# PG03__Qseven_Connector.net
KiCad netlist of a schematic drawn in Altium Designer
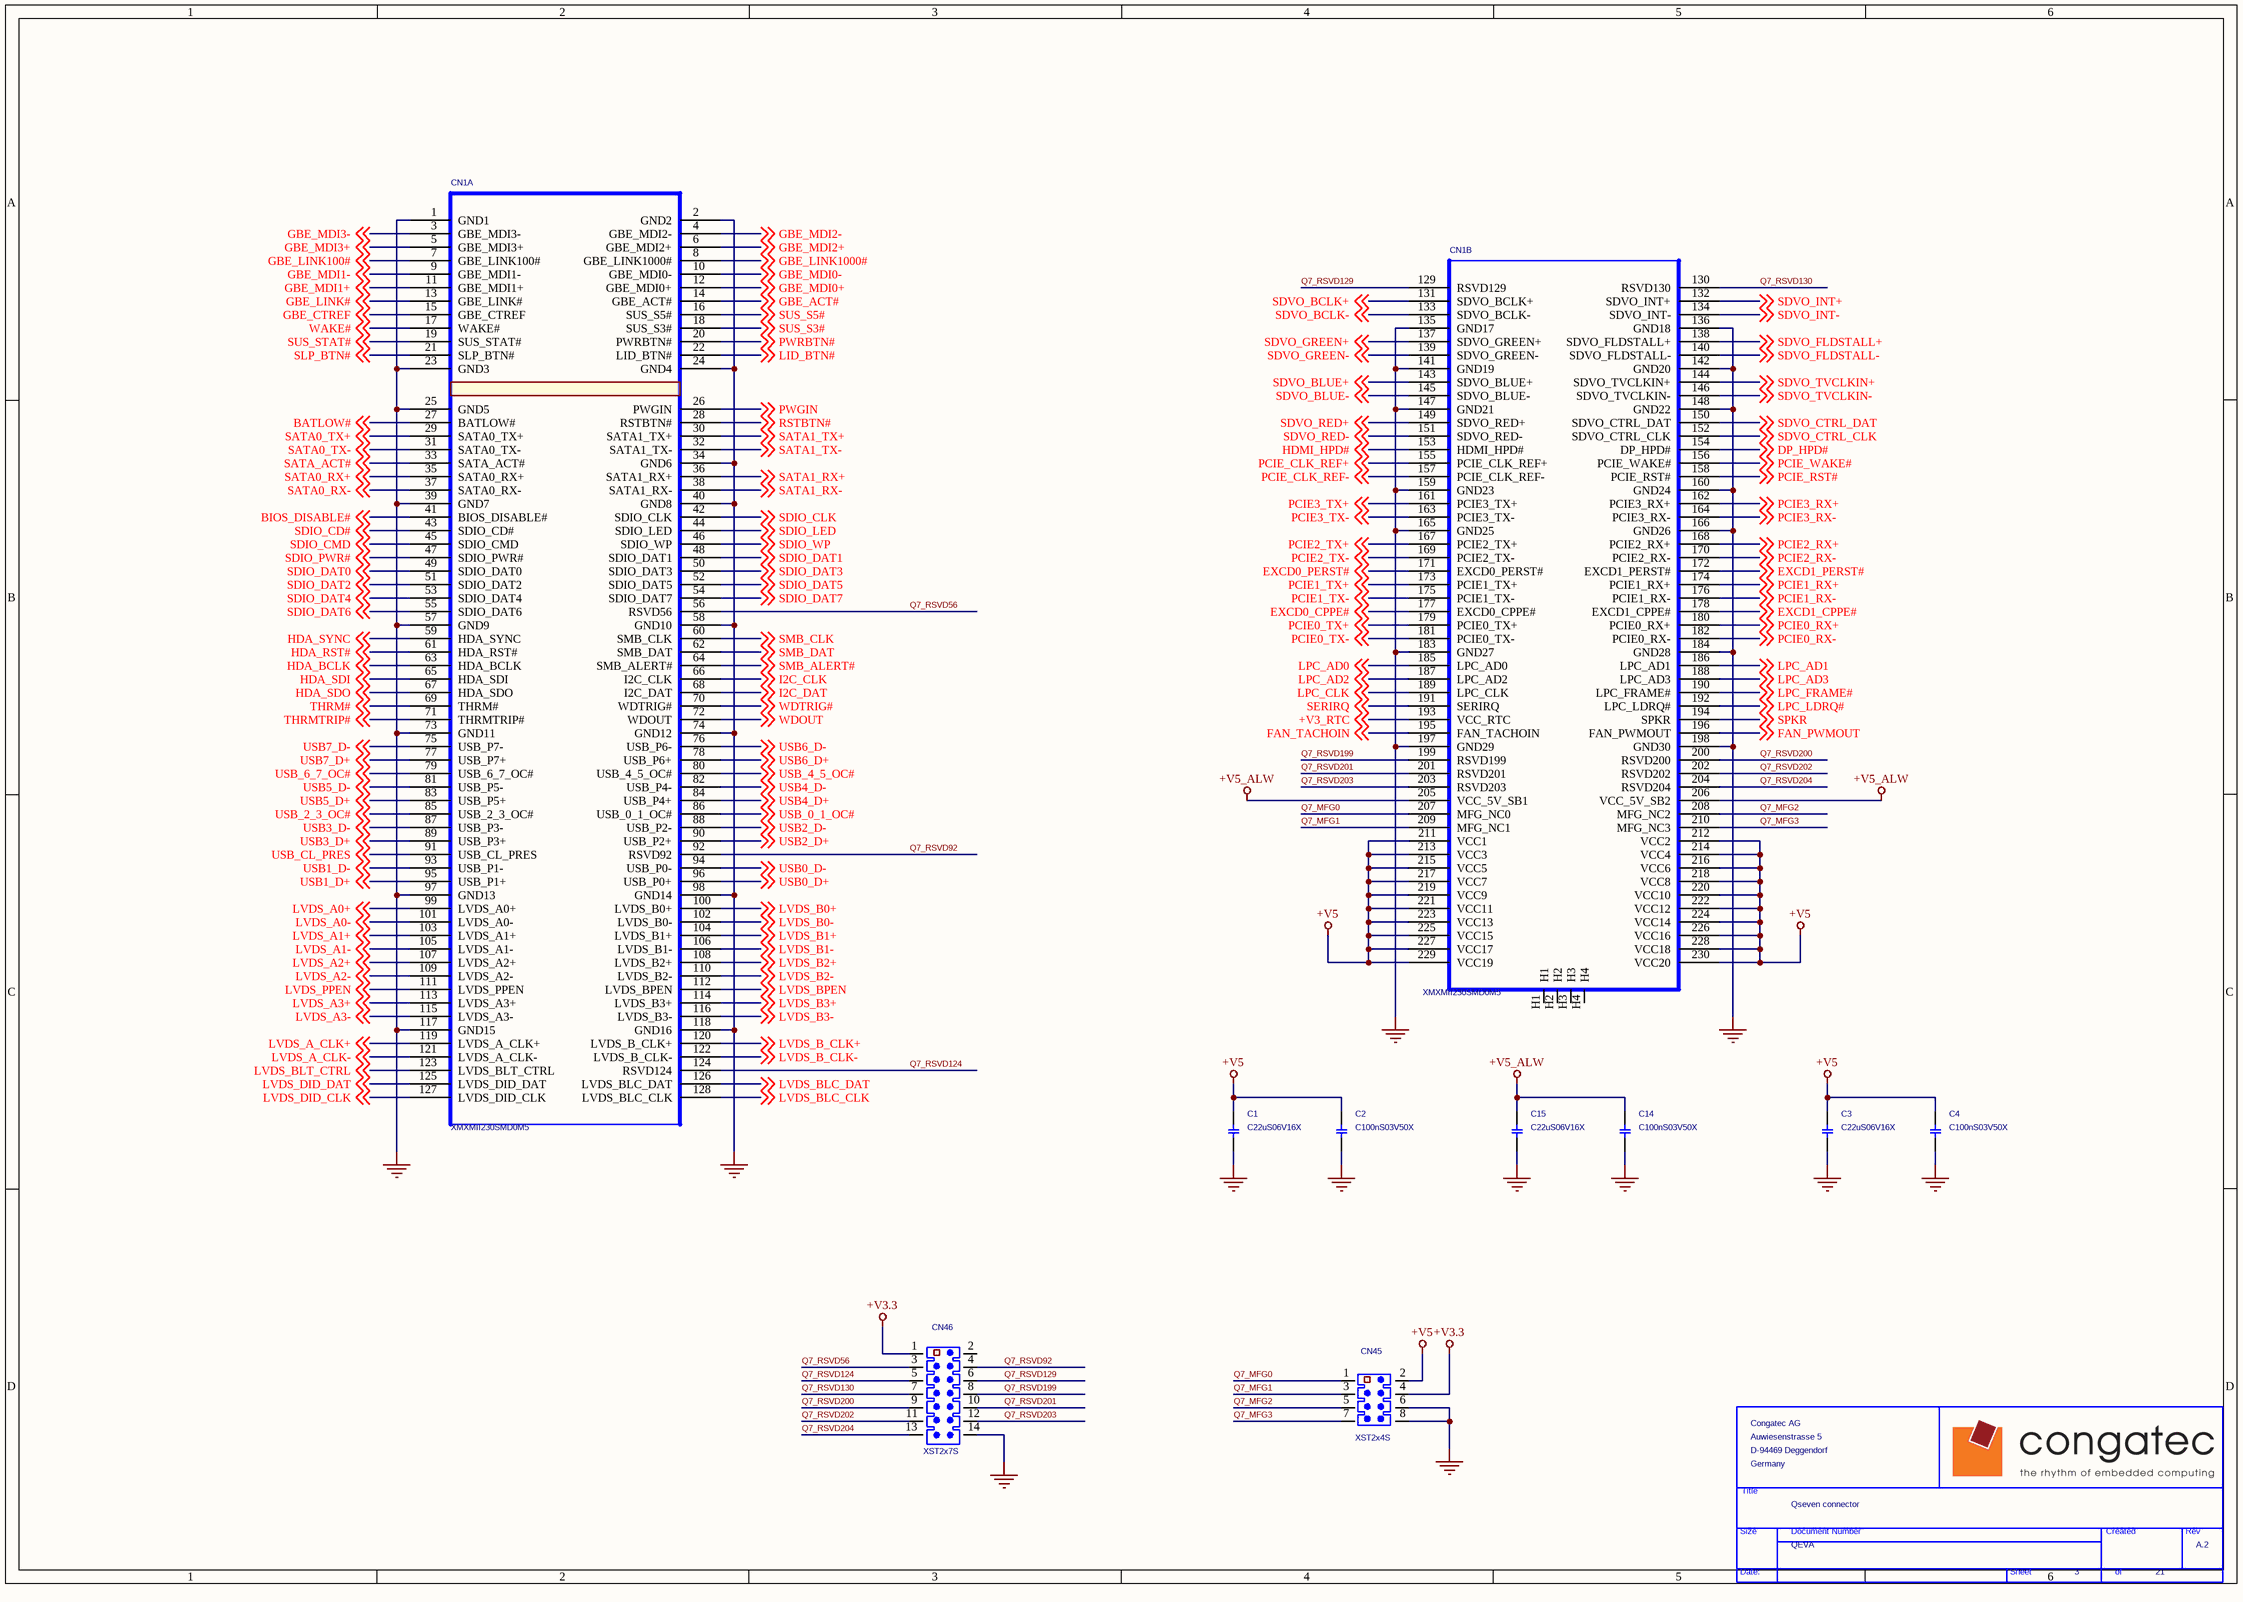
[diagram p0: PG03_ Qseven Connector.SchDoc]

(export (version "E")
  (design (tool "Eeschema 10.0.6"))
  (components
    (comp (ref "C1")
      (value "C22uS06V16X")
      (description "CAP 22uF 16V X5R SMD 1206 MLCC WO/PB")
      (fields (field (name "PART NUMBER") "1100001310") (field (name "TOLERANCE") "20%"))
      (libsource (lib "*") (part "11_C_0"))
    )
    (comp (ref "C2")
      (value "C100nS03V50X")
      (description "CAP 0.1U 50V +-10% SMD 0603 X7R WO/Pb")
      (fields
        (field (name "PART_NUMBER") "41000289")
        (field (name "MANUFACTURE PART NUMBER") "C1608X7R1H104KT223858615649")
      )
      (libsource (lib "*") (part "11_C_0"))
    )
    (comp (ref "C3")
      (value "C22uS06V16X")
      (description "CAP 22uF 16V X5R SMD 1206 MLCC WO/PB")
      (fields (field (name "PART NUMBER") "1100001310") (field (name "TOLERANCE") "20%"))
      (libsource (lib "*") (part "11_C_0"))
    )
    (comp (ref "C4")
      (value "C100nS03V50X")
      (description "CAP 0.1U 50V +-10% SMD 0603 X7R WO/Pb")
      (fields
        (field (name "PART_NUMBER") "41000289")
        (field (name "MANUFACTURE PART NUMBER") "C1608X7R1H104KT223858615649")
      )
      (libsource (lib "*") (part "11_C_0"))
    )
    (comp (ref "C14")
      (value "C100nS03V50X")
      (description "CAP 0.1U 50V +-10% SMD 0603 X7R WO/Pb")
      (fields
        (field (name "PART_NUMBER") "41000289")
        (field (name "MANUFACTURE PART NUMBER") "C1608X7R1H104KT223858615649")
      )
      (libsource (lib "*") (part "11_C_0"))
    )
    (comp (ref "C15")
      (value "C22uS06V16X")
      (description "CAP 22uF 16V X5R SMD 1206 MLCC WO/PB")
      (fields (field (name "PART NUMBER") "1100001310") (field (name "TOLERANCE") "20%"))
      (libsource (lib "*") (part "11_C_0"))
    )
    (comp (ref "CN1")
      (value "XMXMII230SMD0M5")
      (fields (field (name "PART NUMBER") "1654005496") (field (name "PART_NUMBER") "41500262"))
      (libsource (lib "*") (part "Qseven"))
    )
    (comp (ref "CN45")
      (value "XST2x4S")
      (description "PIN HEADER 4*2P 180D(M) 2.54mm DIP WO/Pb")
      (fields
        (field (name "PART_NUMBER") "41500115")
        (field (name "MANUFACTURE PART NUMBER") "201-2*4GS21N22564-08S10B-01G-6/3")
      )
      (libsource (lib "*") (part "1653_JH4X2V_0"))
    )
    (comp (ref "CN46")
      (value "XST2x7S")
      (description "PIN HEADER 7*2P 180D(M) 2.54mm DIP WO/Pb")
      (fields
        (field (name "MANUFACTURE PART NUMBER") "$16530072001130-010-14S21N22564-14S10B-01G-6/3")
        (field (name "PART NUMBER") "1653007200")
      )
      (libsource (lib "*") (part "1653_JH7X2V_0"))
    )
  )
  (nets
    (net (code "1") (name "+V3.3") (class "Default")
      (node (ref "CN45") (pin "4") (pinfunction "4_4") (pintype "passive"))
      (node (ref "CN46") (pin "1") (pinfunction "1_1") (pintype "passive"))
    )
    (net (code "2") (name "+V3_RTC") (class "Default")
      (node (ref "CN1") (pin "193") (pinfunction "VCC_RTC_193") (pintype "passive"))
    )
    (net (code "3") (name "+V5") (class "Default")
      (node (ref "C1") (pin "1") (pinfunction "1_1") (pintype "passive"))
      (node (ref "C2") (pin "1") (pinfunction "1_1") (pintype "passive"))
      (node (ref "C3") (pin "1") (pinfunction "1_1") (pintype "passive"))
      (node (ref "C4") (pin "1") (pinfunction "1_1") (pintype "passive"))
      (node (ref "CN1") (pin "211") (pinfunction "VCC1_211") (pintype "passive"))
      (node (ref "CN1") (pin "212") (pinfunction "VCC2_212") (pintype "passive"))
      (node (ref "CN1") (pin "213") (pinfunction "VCC3_213") (pintype "passive"))
      (node (ref "CN1") (pin "214") (pinfunction "VCC4_214") (pintype "passive"))
      (node (ref "CN1") (pin "215") (pinfunction "VCC5_215") (pintype "passive"))
      (node (ref "CN1") (pin "216") (pinfunction "VCC6_216") (pintype "passive"))
      (node (ref "CN1") (pin "217") (pinfunction "VCC7_217") (pintype "passive"))
      (node (ref "CN1") (pin "218") (pinfunction "VCC8_218") (pintype "passive"))
      (node (ref "CN1") (pin "219") (pinfunction "VCC9_219") (pintype "passive"))
      (node (ref "CN1") (pin "220") (pinfunction "VCC10_220") (pintype "passive"))
      (node (ref "CN1") (pin "221") (pinfunction "VCC11_221") (pintype "passive"))
      (node (ref "CN1") (pin "222") (pinfunction "VCC12_222") (pintype "passive"))
      (node (ref "CN1") (pin "223") (pinfunction "VCC13_223") (pintype "passive"))
      (node (ref "CN1") (pin "224") (pinfunction "VCC14_224") (pintype "passive"))
      (node (ref "CN1") (pin "225") (pinfunction "VCC15_225") (pintype "passive"))
      (node (ref "CN1") (pin "226") (pinfunction "VCC16_226") (pintype "passive"))
      (node (ref "CN1") (pin "227") (pinfunction "VCC17_227") (pintype "passive"))
      (node (ref "CN1") (pin "228") (pinfunction "VCC18_228") (pintype "passive"))
      (node (ref "CN1") (pin "229") (pinfunction "VCC19_229") (pintype "passive"))
      (node (ref "CN1") (pin "230") (pinfunction "VCC20_230") (pintype "passive"))
      (node (ref "CN45") (pin "2") (pinfunction "2_2") (pintype "passive"))
    )
    (net (code "4") (name "+V5_ALW") (class "Default")
      (node (ref "C14") (pin "1") (pinfunction "1_1") (pintype "passive"))
      (node (ref "C15") (pin "1") (pinfunction "1_1") (pintype "passive"))
      (node (ref "CN1") (pin "205") (pinfunction "VCC_5V_SB1_205") (pintype "passive"))
      (node (ref "CN1") (pin "206") (pinfunction "VCC_5V_SB2_206") (pintype "passive"))
    )
    (net (code "5") (name "/Q7_MFG0") (class "Default")
      (node (ref "CN1") (pin "207") (pinfunction "MFG_NC0_207") (pintype "passive"))
      (node (ref "CN45") (pin "1") (pinfunction "1_1") (pintype "passive"))
    )
    (net (code "6") (name "/Q7_MFG1") (class "Default")
      (node (ref "CN1") (pin "209") (pinfunction "MFG_NC1_209") (pintype "passive"))
      (node (ref "CN45") (pin "3") (pinfunction "3_3") (pintype "passive"))
    )
    (net (code "7") (name "/Q7_MFG2") (class "Default")
      (node (ref "CN1") (pin "208") (pinfunction "MFG_NC2_208") (pintype "passive"))
      (node (ref "CN45") (pin "5") (pinfunction "5_5") (pintype "passive"))
    )
    (net (code "8") (name "/Q7_MFG3") (class "Default")
      (node (ref "CN1") (pin "210") (pinfunction "MFG_NC3_210") (pintype "passive"))
      (node (ref "CN45") (pin "7") (pinfunction "7_7") (pintype "passive"))
    )
    (net (code "9") (name "/Q7_RSVD56") (class "Default")
      (node (ref "CN1") (pin "56") (pinfunction "RSVD56_56") (pintype "passive"))
      (node (ref "CN46") (pin "3") (pinfunction "3_3") (pintype "passive"))
    )
    (net (code "10") (name "/Q7_RSVD92") (class "Default")
      (node (ref "CN1") (pin "92") (pinfunction "RSVD92_92") (pintype "passive"))
      (node (ref "CN46") (pin "4") (pinfunction "4_4") (pintype "passive"))
    )
    (net (code "11") (name "/Q7_RSVD124") (class "Default")
      (node (ref "CN1") (pin "124") (pinfunction "RSVD124_124") (pintype "passive"))
      (node (ref "CN46") (pin "5") (pinfunction "5_5") (pintype "passive"))
    )
    (net (code "12") (name "/Q7_RSVD129") (class "Default")
      (node (ref "CN1") (pin "129") (pinfunction "RSVD129_129") (pintype "passive"))
      (node (ref "CN46") (pin "6") (pinfunction "6_6") (pintype "passive"))
    )
    (net (code "13") (name "/Q7_RSVD130") (class "Default")
      (node (ref "CN1") (pin "130") (pinfunction "RSVD130_130") (pintype "passive"))
      (node (ref "CN46") (pin "7") (pinfunction "7_7") (pintype "passive"))
    )
    (net (code "14") (name "/Q7_RSVD199") (class "Default")
      (node (ref "CN1") (pin "199") (pinfunction "RSVD199_199") (pintype "passive"))
      (node (ref "CN46") (pin "8") (pinfunction "8_8") (pintype "passive"))
    )
    (net (code "15") (name "/Q7_RSVD200") (class "Default")
      (node (ref "CN1") (pin "200") (pinfunction "RSVD200_200") (pintype "passive"))
      (node (ref "CN46") (pin "9") (pinfunction "9_9") (pintype "passive"))
    )
    (net (code "16") (name "/Q7_RSVD201") (class "Default")
      (node (ref "CN1") (pin "201") (pinfunction "RSVD201_201") (pintype "passive"))
      (node (ref "CN46") (pin "10") (pinfunction "10_10") (pintype "passive"))
    )
    (net (code "17") (name "/Q7_RSVD202") (class "Default")
      (node (ref "CN1") (pin "202") (pinfunction "RSVD202_202") (pintype "passive"))
      (node (ref "CN46") (pin "11") (pinfunction "11_11") (pintype "passive"))
    )
    (net (code "18") (name "/Q7_RSVD203") (class "Default")
      (node (ref "CN1") (pin "203") (pinfunction "RSVD203_203") (pintype "passive"))
      (node (ref "CN46") (pin "12") (pinfunction "12_12") (pintype "passive"))
    )
    (net (code "19") (name "/Q7_RSVD204") (class "Default")
      (node (ref "CN1") (pin "204") (pinfunction "RSVD204_204") (pintype "passive"))
      (node (ref "CN46") (pin "13") (pinfunction "13_13") (pintype "passive"))
    )
    (net (code "20") (name "BATLOW#") (class "Default")
      (node (ref "CN1") (pin "27") (pinfunction "BATLOW#_27") (pintype "passive"))
    )
    (net (code "21") (name "BIOS_DISABLE#") (class "Default")
      (node (ref "CN1") (pin "41") (pinfunction "BIOS_DISABLE#_41") (pintype "passive"))
    )
    (net (code "22") (name "DP_HPD#") (class "Default")
      (node (ref "CN1") (pin "154") (pinfunction "DP_HPD#_154") (pintype "passive"))
    )
    (net (code "23") (name "EXCD0_CPPE#") (class "Default")
      (node (ref "CN1") (pin "177") (pinfunction "EXCD0_CPPE#_177") (pintype "passive"))
    )
    (net (code "24") (name "EXCD0_PERST#") (class "Default")
      (node (ref "CN1") (pin "171") (pinfunction "EXCD0_PERST#_171") (pintype "passive"))
    )
    (net (code "25") (name "EXCD1_CPPE#") (class "Default")
      (node (ref "CN1") (pin "178") (pinfunction "EXCD1_CPPE#_178") (pintype "passive"))
    )
    (net (code "26") (name "EXCD1_PERST#") (class "Default")
      (node (ref "CN1") (pin "172") (pinfunction "EXCD1_PERST#_172") (pintype "passive"))
    )
    (net (code "27") (name "FAN_PWMOUT") (class "Default")
      (node (ref "CN1") (pin "196") (pinfunction "FAN_PWMOUT_196") (pintype "passive"))
    )
    (net (code "28") (name "FAN_TACHOIN") (class "Default")
      (node (ref "CN1") (pin "195") (pinfunction "FAN_TACHOIN_195") (pintype "passive"))
    )
    (net (code "29") (name "GBE_ACT#") (class "Default")
      (node (ref "CN1") (pin "14") (pinfunction "GBE_ACT#_14") (pintype "passive"))
    )
    (net (code "30") (name "GBE_CTREF") (class "Default")
      (node (ref "CN1") (pin "15") (pinfunction "GBE_CTREF_15") (pintype "passive"))
    )
    (net (code "31") (name "GBE_LINK#") (class "Default")
      (node (ref "CN1") (pin "13") (pinfunction "GBE_LINK#_13") (pintype "passive"))
    )
    (net (code "32") (name "GBE_LINK100#") (class "Default")
      (node (ref "CN1") (pin "7") (pinfunction "GBE_LINK100#_7") (pintype "passive"))
    )
    (net (code "33") (name "GBE_LINK1000#") (class "Default")
      (node (ref "CN1") (pin "8") (pinfunction "GBE_LINK1000#_8") (pintype "passive"))
    )
    (net (code "34") (name "GBE_MDI0+") (class "Default")
      (node (ref "CN1") (pin "12") (pinfunction "GBE_MDI0+_12") (pintype "passive"))
    )
    (net (code "35") (name "GBE_MDI0-") (class "Default")
      (node (ref "CN1") (pin "10") (pinfunction "GBE_MDI0-_10") (pintype "passive"))
    )
    (net (code "36") (name "GBE_MDI1+") (class "Default")
      (node (ref "CN1") (pin "11") (pinfunction "GBE_MDI1+_11") (pintype "passive"))
    )
    (net (code "37") (name "GBE_MDI1-") (class "Default")
      (node (ref "CN1") (pin "9") (pinfunction "GBE_MDI1-_9") (pintype "passive"))
    )
    (net (code "38") (name "GBE_MDI2+") (class "Default")
      (node (ref "CN1") (pin "6") (pinfunction "GBE_MDI2+_6") (pintype "passive"))
    )
    (net (code "39") (name "GBE_MDI2-") (class "Default")
      (node (ref "CN1") (pin "4") (pinfunction "GBE_MDI2-_4") (pintype "passive"))
    )
    (net (code "40") (name "GBE_MDI3+") (class "Default")
      (node (ref "CN1") (pin "5") (pinfunction "GBE_MDI3+_5") (pintype "passive"))
    )
    (net (code "41") (name "GBE_MDI3-") (class "Default")
      (node (ref "CN1") (pin "3") (pinfunction "GBE_MDI3-_3") (pintype "passive"))
    )
    (net (code "42") (name "GND") (class "Default")
      (node (ref "C1") (pin "2") (pinfunction "2_2") (pintype "passive"))
      (node (ref "C14") (pin "2") (pinfunction "2_2") (pintype "passive"))
      (node (ref "C15") (pin "2") (pinfunction "2_2") (pintype "passive"))
      (node (ref "C2") (pin "2") (pinfunction "2_2") (pintype "passive"))
      (node (ref "C3") (pin "2") (pinfunction "2_2") (pintype "passive"))
      (node (ref "C4") (pin "2") (pinfunction "2_2") (pintype "passive"))
      (node (ref "CN1") (pin "1") (pinfunction "GND1_1") (pintype "passive"))
      (node (ref "CN1") (pin "117") (pinfunction "GND15_117") (pintype "passive"))
      (node (ref "CN1") (pin "118") (pinfunction "GND16_118") (pintype "passive"))
      (node (ref "CN1") (pin "135") (pinfunction "GND17_135") (pintype "passive"))
      (node (ref "CN1") (pin "136") (pinfunction "GND18_136") (pintype "passive"))
      (node (ref "CN1") (pin "141") (pinfunction "GND19_141") (pintype "passive"))
      (node (ref "CN1") (pin "142") (pinfunction "GND20_142") (pintype "passive"))
      (node (ref "CN1") (pin "147") (pinfunction "GND21_147") (pintype "passive"))
      (node (ref "CN1") (pin "148") (pinfunction "GND22_148") (pintype "passive"))
      (node (ref "CN1") (pin "159") (pinfunction "GND23_159") (pintype "passive"))
      (node (ref "CN1") (pin "160") (pinfunction "GND24_160") (pintype "passive"))
      (node (ref "CN1") (pin "165") (pinfunction "GND25_165") (pintype "passive"))
      (node (ref "CN1") (pin "166") (pinfunction "GND26_166") (pintype "passive"))
      (node (ref "CN1") (pin "183") (pinfunction "GND27_183") (pintype "passive"))
      (node (ref "CN1") (pin "184") (pinfunction "GND28_184") (pintype "passive"))
      (node (ref "CN1") (pin "197") (pinfunction "GND29_197") (pintype "passive"))
      (node (ref "CN1") (pin "198") (pinfunction "GND30_198") (pintype "passive"))
      (node (ref "CN1") (pin "2") (pinfunction "GND2_2") (pintype "passive"))
      (node (ref "CN1") (pin "23") (pinfunction "GND3_23") (pintype "passive"))
      (node (ref "CN1") (pin "24") (pinfunction "GND4_24") (pintype "passive"))
      (node (ref "CN1") (pin "25") (pinfunction "GND5_25") (pintype "passive"))
      (node (ref "CN1") (pin "34") (pinfunction "GND6_34") (pintype "passive"))
      (node (ref "CN1") (pin "39") (pinfunction "GND7_39") (pintype "passive"))
      (node (ref "CN1") (pin "40") (pinfunction "GND8_40") (pintype "passive"))
      (node (ref "CN1") (pin "57") (pinfunction "GND9_57") (pintype "passive"))
      (node (ref "CN1") (pin "58") (pinfunction "GND10_58") (pintype "passive"))
      (node (ref "CN1") (pin "73") (pinfunction "GND11_73") (pintype "passive"))
      (node (ref "CN1") (pin "74") (pinfunction "GND12_74") (pintype "passive"))
      (node (ref "CN1") (pin "97") (pinfunction "GND13_97") (pintype "passive"))
      (node (ref "CN1") (pin "98") (pinfunction "GND14_98") (pintype "passive"))
      (node (ref "CN45") (pin "6") (pinfunction "6_6") (pintype "passive"))
      (node (ref "CN45") (pin "8") (pinfunction "8_8") (pintype "passive"))
      (node (ref "CN46") (pin "14") (pinfunction "14_14") (pintype "passive"))
    )
    (net (code "43") (name "HDA_BCLK") (class "Default")
      (node (ref "CN1") (pin "63") (pinfunction "HDA_BCLK_63") (pintype "passive"))
    )
    (net (code "44") (name "HDA_RST#") (class "Default")
      (node (ref "CN1") (pin "61") (pinfunction "HDA_RST#_61") (pintype "passive"))
    )
    (net (code "45") (name "HDA_SDI") (class "Default")
      (node (ref "CN1") (pin "65") (pinfunction "HDA_SDI_65") (pintype "passive"))
    )
    (net (code "46") (name "HDA_SDO") (class "Default")
      (node (ref "CN1") (pin "67") (pinfunction "HDA_SDO_67") (pintype "passive"))
    )
    (net (code "47") (name "HDA_SYNC") (class "Default")
      (node (ref "CN1") (pin "59") (pinfunction "HDA_SYNC_59") (pintype "passive"))
    )
    (net (code "48") (name "HDMI_HPD#") (class "Default")
      (node (ref "CN1") (pin "153") (pinfunction "HDMI_HPD#_153") (pintype "passive"))
    )
    (net (code "49") (name "I2C_CLK") (class "Default")
      (node (ref "CN1") (pin "66") (pinfunction "I2C_CLK_66") (pintype "passive"))
    )
    (net (code "50") (name "I2C_DAT") (class "Default")
      (node (ref "CN1") (pin "68") (pinfunction "I2C_DAT_68") (pintype "passive"))
    )
    (net (code "51") (name "LID_BTN#") (class "Default")
      (node (ref "CN1") (pin "22") (pinfunction "LID_BTN#_22") (pintype "passive"))
    )
    (net (code "52") (name "LPC_AD0") (class "Default")
      (node (ref "CN1") (pin "185") (pinfunction "LPC_AD0_185") (pintype "passive"))
    )
    (net (code "53") (name "LPC_AD1") (class "Default")
      (node (ref "CN1") (pin "186") (pinfunction "LPC_AD1_186") (pintype "passive"))
    )
    (net (code "54") (name "LPC_AD2") (class "Default")
      (node (ref "CN1") (pin "187") (pinfunction "LPC_AD2_187") (pintype "passive"))
    )
    (net (code "55") (name "LPC_AD3") (class "Default")
      (node (ref "CN1") (pin "188") (pinfunction "LPC_AD3_188") (pintype "passive"))
    )
    (net (code "56") (name "LPC_CLK") (class "Default")
      (node (ref "CN1") (pin "189") (pinfunction "LPC_CLK_189") (pintype "passive"))
    )
    (net (code "57") (name "LPC_FRAME#") (class "Default")
      (node (ref "CN1") (pin "190") (pinfunction "LPC_FRAME#_190") (pintype "passive"))
    )
    (net (code "58") (name "LPC_LDRQ#") (class "Default")
      (node (ref "CN1") (pin "192") (pinfunction "LPC_LDRQ#_192") (pintype "passive"))
    )
    (net (code "59") (name "LVDS_A0+") (class "Default")
      (node (ref "CN1") (pin "99") (pinfunction "LVDS_A0+_99") (pintype "passive"))
    )
    (net (code "60") (name "LVDS_A0-") (class "Default")
      (node (ref "CN1") (pin "101") (pinfunction "LVDS_A0-_101") (pintype "passive"))
    )
    (net (code "61") (name "LVDS_A1+") (class "Default")
      (node (ref "CN1") (pin "103") (pinfunction "LVDS_A1+_103") (pintype "passive"))
    )
    (net (code "62") (name "LVDS_A1-") (class "Default")
      (node (ref "CN1") (pin "105") (pinfunction "LVDS_A1-_105") (pintype "passive"))
    )
    (net (code "63") (name "LVDS_A2+") (class "Default")
      (node (ref "CN1") (pin "107") (pinfunction "LVDS_A2+_107") (pintype "passive"))
    )
    (net (code "64") (name "LVDS_A2-") (class "Default")
      (node (ref "CN1") (pin "109") (pinfunction "LVDS_A2-_109") (pintype "passive"))
    )
    (net (code "65") (name "LVDS_A3+") (class "Default")
      (node (ref "CN1") (pin "113") (pinfunction "LVDS_A3+_113") (pintype "passive"))
    )
    (net (code "66") (name "LVDS_A3-") (class "Default")
      (node (ref "CN1") (pin "115") (pinfunction "LVDS_A3-_115") (pintype "passive"))
    )
    (net (code "67") (name "LVDS_A_CLK+") (class "Default")
      (node (ref "CN1") (pin "119") (pinfunction "LVDS_A_CLK+_119") (pintype "passive"))
    )
    (net (code "68") (name "LVDS_A_CLK-") (class "Default")
      (node (ref "CN1") (pin "121") (pinfunction "LVDS_A_CLK-_121") (pintype "passive"))
    )
    (net (code "69") (name "LVDS_B0+") (class "Default")
      (node (ref "CN1") (pin "100") (pinfunction "LVDS_B0+_100") (pintype "passive"))
    )
    (net (code "70") (name "LVDS_B0-") (class "Default")
      (node (ref "CN1") (pin "102") (pinfunction "LVDS_B0-_102") (pintype "passive"))
    )
    (net (code "71") (name "LVDS_B1+") (class "Default")
      (node (ref "CN1") (pin "104") (pinfunction "LVDS_B1+_104") (pintype "passive"))
    )
    (net (code "72") (name "LVDS_B1-") (class "Default")
      (node (ref "CN1") (pin "106") (pinfunction "LVDS_B1-_106") (pintype "passive"))
    )
    (net (code "73") (name "LVDS_B2+") (class "Default")
      (node (ref "CN1") (pin "108") (pinfunction "LVDS_B2+_108") (pintype "passive"))
    )
    (net (code "74") (name "LVDS_B2-") (class "Default")
      (node (ref "CN1") (pin "110") (pinfunction "LVDS_B2-_110") (pintype "passive"))
    )
    (net (code "75") (name "LVDS_B3+") (class "Default")
      (node (ref "CN1") (pin "114") (pinfunction "LVDS_B3+_114") (pintype "passive"))
    )
    (net (code "76") (name "LVDS_B3-") (class "Default")
      (node (ref "CN1") (pin "116") (pinfunction "LVDS_B3-_116") (pintype "passive"))
    )
    (net (code "77") (name "LVDS_BLC_CLK") (class "Default")
      (node (ref "CN1") (pin "128") (pinfunction "LVDS_BLC_CLK_128") (pintype "passive"))
    )
    (net (code "78") (name "LVDS_BLC_DAT") (class "Default")
      (node (ref "CN1") (pin "126") (pinfunction "LVDS_BLC_DAT_126") (pintype "passive"))
    )
    (net (code "79") (name "LVDS_BLT_CTRL") (class "Default")
      (node (ref "CN1") (pin "123") (pinfunction "LVDS_BLT_CTRL_123") (pintype "passive"))
    )
    (net (code "80") (name "LVDS_BPEN") (class "Default")
      (node (ref "CN1") (pin "112") (pinfunction "LVDS_BPEN_112") (pintype "passive"))
    )
    (net (code "81") (name "LVDS_B_CLK+") (class "Default")
      (node (ref "CN1") (pin "120") (pinfunction "LVDS_B_CLK+_120") (pintype "passive"))
    )
    (net (code "82") (name "LVDS_B_CLK-") (class "Default")
      (node (ref "CN1") (pin "122") (pinfunction "LVDS_B_CLK-_122") (pintype "passive"))
    )
    (net (code "83") (name "LVDS_DID_CLK") (class "Default")
      (node (ref "CN1") (pin "127") (pinfunction "LVDS_DID_CLK_127") (pintype "passive"))
    )
    (net (code "84") (name "LVDS_DID_DAT") (class "Default")
      (node (ref "CN1") (pin "125") (pinfunction "LVDS_DID_DAT_125") (pintype "passive"))
    )
    (net (code "85") (name "LVDS_PPEN") (class "Default")
      (node (ref "CN1") (pin "111") (pinfunction "LVDS_PPEN_111") (pintype "passive"))
    )
    (net (code "86") (name "PCIE0_RX+") (class "Default")
      (node (ref "CN1") (pin "180") (pinfunction "PCIE0_RX+_180") (pintype "passive"))
    )
    (net (code "87") (name "PCIE0_RX-") (class "Default")
      (node (ref "CN1") (pin "182") (pinfunction "PCIE0_RX-_182") (pintype "passive"))
    )
    (net (code "88") (name "PCIE0_TX+") (class "Default")
      (node (ref "CN1") (pin "179") (pinfunction "PCIE0_TX+_179") (pintype "passive"))
    )
    (net (code "89") (name "PCIE0_TX-") (class "Default")
      (node (ref "CN1") (pin "181") (pinfunction "PCIE0_TX-_181") (pintype "passive"))
    )
    (net (code "90") (name "PCIE1_RX+") (class "Default")
      (node (ref "CN1") (pin "174") (pinfunction "PCIE1_RX+_174") (pintype "passive"))
    )
    (net (code "91") (name "PCIE1_RX-") (class "Default")
      (node (ref "CN1") (pin "176") (pinfunction "PCIE1_RX-_176") (pintype "passive"))
    )
    (net (code "92") (name "PCIE1_TX+") (class "Default")
      (node (ref "CN1") (pin "173") (pinfunction "PCIE1_TX+_173") (pintype "passive"))
    )
    (net (code "93") (name "PCIE1_TX-") (class "Default")
      (node (ref "CN1") (pin "175") (pinfunction "PCIE1_TX-_175") (pintype "passive"))
    )
    (net (code "94") (name "PCIE2_RX+") (class "Default")
      (node (ref "CN1") (pin "168") (pinfunction "PCIE2_RX+_168") (pintype "passive"))
    )
    (net (code "95") (name "PCIE2_RX-") (class "Default")
      (node (ref "CN1") (pin "170") (pinfunction "PCIE2_RX-_170") (pintype "passive"))
    )
    (net (code "96") (name "PCIE2_TX+") (class "Default")
      (node (ref "CN1") (pin "167") (pinfunction "PCIE2_TX+_167") (pintype "passive"))
    )
    (net (code "97") (name "PCIE2_TX-") (class "Default")
      (node (ref "CN1") (pin "169") (pinfunction "PCIE2_TX-_169") (pintype "passive"))
    )
    (net (code "98") (name "PCIE3_RX+") (class "Default")
      (node (ref "CN1") (pin "162") (pinfunction "PCIE3_RX+_162") (pintype "passive"))
    )
    (net (code "99") (name "PCIE3_RX-") (class "Default")
      (node (ref "CN1") (pin "164") (pinfunction "PCIE3_RX-_164") (pintype "passive"))
    )
    (net (code "100") (name "PCIE3_TX+") (class "Default")
      (node (ref "CN1") (pin "161") (pinfunction "PCIE3_TX+_161") (pintype "passive"))
    )
    (net (code "101") (name "PCIE3_TX-") (class "Default")
      (node (ref "CN1") (pin "163") (pinfunction "PCIE3_TX-_163") (pintype "passive"))
    )
    (net (code "102") (name "PCIE_CLK_REF+") (class "Default")
      (node (ref "CN1") (pin "155") (pinfunction "PCIE_CLK_REF+_155") (pintype "passive"))
    )
    (net (code "103") (name "PCIE_CLK_REF-") (class "Default")
      (node (ref "CN1") (pin "157") (pinfunction "PCIE_CLK_REF-_157") (pintype "passive"))
    )
    (net (code "104") (name "PCIE_RST#") (class "Default")
      (node (ref "CN1") (pin "158") (pinfunction "PCIE_RST#_158") (pintype "passive"))
    )
    (net (code "105") (name "PCIE_WAKE#") (class "Default")
      (node (ref "CN1") (pin "156") (pinfunction "PCIE_WAKE#_156") (pintype "passive"))
    )
    (net (code "106") (name "PWGIN") (class "Default")
      (node (ref "CN1") (pin "26") (pinfunction "PWGIN_26") (pintype "passive"))
    )
    (net (code "107") (name "PWRBTN#") (class "Default")
      (node (ref "CN1") (pin "20") (pinfunction "PWRBTN#_20") (pintype "passive"))
    )
    (net (code "108") (name "RSTBTN#") (class "Default")
      (node (ref "CN1") (pin "28") (pinfunction "RSTBTN#_28") (pintype "passive"))
    )
    (net (code "109") (name "SATA0_RX+") (class "Default")
      (node (ref "CN1") (pin "35") (pinfunction "SATA0_RX+_35") (pintype "passive"))
    )
    (net (code "110") (name "SATA0_RX-") (class "Default")
      (node (ref "CN1") (pin "37") (pinfunction "SATA0_RX-_37") (pintype "passive"))
    )
    (net (code "111") (name "SATA0_TX+") (class "Default")
      (node (ref "CN1") (pin "29") (pinfunction "SATA0_TX+_29") (pintype "passive"))
    )
    (net (code "112") (name "SATA0_TX-") (class "Default")
      (node (ref "CN1") (pin "31") (pinfunction "SATA0_TX-_31") (pintype "passive"))
    )
    (net (code "113") (name "SATA1_RX+") (class "Default")
      (node (ref "CN1") (pin "36") (pinfunction "SATA1_RX+_36") (pintype "passive"))
    )
    (net (code "114") (name "SATA1_RX-") (class "Default")
      (node (ref "CN1") (pin "38") (pinfunction "SATA1_RX-_38") (pintype "passive"))
    )
    (net (code "115") (name "SATA1_TX+") (class "Default")
      (node (ref "CN1") (pin "30") (pinfunction "SATA1_TX+_30") (pintype "passive"))
    )
    (net (code "116") (name "SATA1_TX-") (class "Default")
      (node (ref "CN1") (pin "32") (pinfunction "SATA1_TX-_32") (pintype "passive"))
    )
    (net (code "117") (name "SATA_ACT#") (class "Default")
      (node (ref "CN1") (pin "33") (pinfunction "SATA_ACT#_33") (pintype "passive"))
    )
    (net (code "118") (name "SDIO_CD#") (class "Default")
      (node (ref "CN1") (pin "43") (pinfunction "SDIO_CD#_43") (pintype "passive"))
    )
    (net (code "119") (name "SDIO_CLK") (class "Default")
      (node (ref "CN1") (pin "42") (pinfunction "SDIO_CLK_42") (pintype "passive"))
    )
    (net (code "120") (name "SDIO_CMD") (class "Default")
      (node (ref "CN1") (pin "45") (pinfunction "SDIO_CMD_45") (pintype "passive"))
    )
    (net (code "121") (name "SDIO_DAT0") (class "Default")
      (node (ref "CN1") (pin "49") (pinfunction "SDIO_DAT0_49") (pintype "passive"))
    )
    (net (code "122") (name "SDIO_DAT1") (class "Default")
      (node (ref "CN1") (pin "48") (pinfunction "SDIO_DAT1_48") (pintype "passive"))
    )
    (net (code "123") (name "SDIO_DAT2") (class "Default")
      (node (ref "CN1") (pin "51") (pinfunction "SDIO_DAT2_51") (pintype "passive"))
    )
    (net (code "124") (name "SDIO_DAT3") (class "Default")
      (node (ref "CN1") (pin "50") (pinfunction "SDIO_DAT3_50") (pintype "passive"))
    )
    (net (code "125") (name "SDIO_DAT4") (class "Default")
      (node (ref "CN1") (pin "53") (pinfunction "SDIO_DAT4_53") (pintype "passive"))
    )
    (net (code "126") (name "SDIO_DAT5") (class "Default")
      (node (ref "CN1") (pin "52") (pinfunction "SDIO_DAT5_52") (pintype "passive"))
    )
    (net (code "127") (name "SDIO_DAT6") (class "Default")
      (node (ref "CN1") (pin "55") (pinfunction "SDIO_DAT6_55") (pintype "passive"))
    )
    (net (code "128") (name "SDIO_DAT7") (class "Default")
      (node (ref "CN1") (pin "54") (pinfunction "SDIO_DAT7_54") (pintype "passive"))
    )
    (net (code "129") (name "SDIO_LED") (class "Default")
      (node (ref "CN1") (pin "44") (pinfunction "SDIO_LED_44") (pintype "passive"))
    )
    (net (code "130") (name "SDIO_PWR#") (class "Default")
      (node (ref "CN1") (pin "47") (pinfunction "SDIO_PWR#_47") (pintype "passive"))
    )
    (net (code "131") (name "SDIO_WP") (class "Default")
      (node (ref "CN1") (pin "46") (pinfunction "SDIO_WP_46") (pintype "passive"))
    )
    (net (code "132") (name "SDVO_BCLK+") (class "Default")
      (node (ref "CN1") (pin "131") (pinfunction "SDVO_BCLK+_131") (pintype "passive"))
    )
    (net (code "133") (name "SDVO_BCLK-") (class "Default")
      (node (ref "CN1") (pin "133") (pinfunction "SDVO_BCLK-_133") (pintype "passive"))
    )
    (net (code "134") (name "SDVO_BLUE+") (class "Default")
      (node (ref "CN1") (pin "143") (pinfunction "SDVO_BLUE+_143") (pintype "passive"))
    )
    (net (code "135") (name "SDVO_BLUE-") (class "Default")
      (node (ref "CN1") (pin "145") (pinfunction "SDVO_BLUE-_145") (pintype "passive"))
    )
    (net (code "136") (name "SDVO_CTRL_CLK") (class "Default")
      (node (ref "CN1") (pin "152") (pinfunction "SDVO_CTRL_CLK_152") (pintype "passive"))
    )
    (net (code "137") (name "SDVO_CTRL_DAT") (class "Default")
      (node (ref "CN1") (pin "150") (pinfunction "SDVO_CTRL_DAT_150") (pintype "passive"))
    )
    (net (code "138") (name "SDVO_FLDSTALL+") (class "Default")
      (node (ref "CN1") (pin "138") (pinfunction "SDVO_FLDSTALL+_138") (pintype "passive"))
    )
    (net (code "139") (name "SDVO_FLDSTALL-") (class "Default")
      (node (ref "CN1") (pin "140") (pinfunction "SDVO_FLDSTALL-_140") (pintype "passive"))
    )
    (net (code "140") (name "SDVO_GREEN+") (class "Default")
      (node (ref "CN1") (pin "137") (pinfunction "SDVO_GREEN+_137") (pintype "passive"))
    )
    (net (code "141") (name "SDVO_GREEN-") (class "Default")
      (node (ref "CN1") (pin "139") (pinfunction "SDVO_GREEN-_139") (pintype "passive"))
    )
    (net (code "142") (name "SDVO_INT+") (class "Default")
      (node (ref "CN1") (pin "132") (pinfunction "SDVO_INT+_132") (pintype "passive"))
    )
    (net (code "143") (name "SDVO_INT-") (class "Default")
      (node (ref "CN1") (pin "134") (pinfunction "SDVO_INT-_134") (pintype "passive"))
    )
    (net (code "144") (name "SDVO_RED+") (class "Default")
      (node (ref "CN1") (pin "149") (pinfunction "SDVO_RED+_149") (pintype "passive"))
    )
    (net (code "145") (name "SDVO_RED-") (class "Default")
      (node (ref "CN1") (pin "151") (pinfunction "SDVO_RED-_151") (pintype "passive"))
    )
    (net (code "146") (name "SDVO_TVCLKIN+") (class "Default")
      (node (ref "CN1") (pin "144") (pinfunction "SDVO_TVCLKIN+_144") (pintype "passive"))
    )
    (net (code "147") (name "SDVO_TVCLKIN-") (class "Default")
      (node (ref "CN1") (pin "146") (pinfunction "SDVO_TVCLKIN-_146") (pintype "passive"))
    )
    (net (code "148") (name "SERIRQ") (class "Default")
      (node (ref "CN1") (pin "191") (pinfunction "SERIRQ_191") (pintype "passive"))
    )
    (net (code "149") (name "SLP_BTN#") (class "Default")
      (node (ref "CN1") (pin "21") (pinfunction "SLP_BTN#_21") (pintype "passive"))
    )
    (net (code "150") (name "SMB_ALERT#") (class "Default")
      (node (ref "CN1") (pin "64") (pinfunction "SMB_ALERT#_64") (pintype "passive"))
    )
    (net (code "151") (name "SMB_CLK") (class "Default")
      (node (ref "CN1") (pin "60") (pinfunction "SMB_CLK_60") (pintype "passive"))
    )
    (net (code "152") (name "SMB_DAT") (class "Default")
      (node (ref "CN1") (pin "62") (pinfunction "SMB_DAT_62") (pintype "passive"))
    )
    (net (code "153") (name "SPKR") (class "Default")
      (node (ref "CN1") (pin "194") (pinfunction "SPKR_194") (pintype "passive"))
    )
    (net (code "154") (name "SUS_S3#") (class "Default")
      (node (ref "CN1") (pin "18") (pinfunction "SUS_S3#_18") (pintype "passive"))
    )
    (net (code "155") (name "SUS_S5#") (class "Default")
      (node (ref "CN1") (pin "16") (pinfunction "SUS_S5#_16") (pintype "passive"))
    )
    (net (code "156") (name "SUS_STAT#") (class "Default")
      (node (ref "CN1") (pin "19") (pinfunction "SUS_STAT#_19") (pintype "passive"))
    )
    (net (code "157") (name "THRM#") (class "Default")
      (node (ref "CN1") (pin "69") (pinfunction "THRM#_69") (pintype "passive"))
    )
    (net (code "158") (name "THRMTRIP#") (class "Default")
      (node (ref "CN1") (pin "71") (pinfunction "THRMTRIP#_71") (pintype "passive"))
    )
    (net (code "159") (name "USB0_D+") (class "Default")
      (node (ref "CN1") (pin "96") (pinfunction "USB_P0+_96") (pintype "passive"))
    )
    (net (code "160") (name "USB0_D-") (class "Default")
      (node (ref "CN1") (pin "94") (pinfunction "USB_P0-_94") (pintype "passive"))
    )
    (net (code "161") (name "USB1_D+") (class "Default")
      (node (ref "CN1") (pin "95") (pinfunction "USB_P1+_95") (pintype "passive"))
    )
    (net (code "162") (name "USB1_D-") (class "Default")
      (node (ref "CN1") (pin "93") (pinfunction "USB_P1-_93") (pintype "passive"))
    )
    (net (code "163") (name "USB2_D+") (class "Default")
      (node (ref "CN1") (pin "90") (pinfunction "USB_P2+_90") (pintype "passive"))
    )
    (net (code "164") (name "USB2_D-") (class "Default")
      (node (ref "CN1") (pin "88") (pinfunction "USB_P2-_88") (pintype "passive"))
    )
    (net (code "165") (name "USB3_D+") (class "Default")
      (node (ref "CN1") (pin "89") (pinfunction "USB_P3+_89") (pintype "passive"))
    )
    (net (code "166") (name "USB3_D-") (class "Default")
      (node (ref "CN1") (pin "87") (pinfunction "USB_P3-_87") (pintype "passive"))
    )
    (net (code "167") (name "USB4_D+") (class "Default")
      (node (ref "CN1") (pin "84") (pinfunction "USB_P4+_84") (pintype "passive"))
    )
    (net (code "168") (name "USB4_D-") (class "Default")
      (node (ref "CN1") (pin "82") (pinfunction "USB_P4-_82") (pintype "passive"))
    )
    (net (code "169") (name "USB5_D+") (class "Default")
      (node (ref "CN1") (pin "83") (pinfunction "USB_P5+_83") (pintype "passive"))
    )
    (net (code "170") (name "USB5_D-") (class "Default")
      (node (ref "CN1") (pin "81") (pinfunction "USB_P5-_81") (pintype "passive"))
    )
    (net (code "171") (name "USB6_D+") (class "Default")
      (node (ref "CN1") (pin "78") (pinfunction "USB_P6+_78") (pintype "passive"))
    )
    (net (code "172") (name "USB6_D-") (class "Default")
      (node (ref "CN1") (pin "76") (pinfunction "USB_P6-_76") (pintype "passive"))
    )
    (net (code "173") (name "USB7_D+") (class "Default")
      (node (ref "CN1") (pin "77") (pinfunction "USB_P7+_77") (pintype "passive"))
    )
    (net (code "174") (name "USB7_D-") (class "Default")
      (node (ref "CN1") (pin "75") (pinfunction "USB_P7-_75") (pintype "passive"))
    )
    (net (code "175") (name "USB_0_1_OC#") (class "Default")
      (node (ref "CN1") (pin "86") (pinfunction "USB_0_1_OC#_86") (pintype "passive"))
    )
    (net (code "176") (name "USB_2_3_OC#") (class "Default")
      (node (ref "CN1") (pin "85") (pinfunction "USB_2_3_OC#_85") (pintype "passive"))
    )
    (net (code "177") (name "USB_4_5_OC#") (class "Default")
      (node (ref "CN1") (pin "80") (pinfunction "USB_4_5_OC#_80") (pintype "passive"))
    )
    (net (code "178") (name "USB_6_7_OC#") (class "Default")
      (node (ref "CN1") (pin "79") (pinfunction "USB_6_7_OC#_79") (pintype "passive"))
    )
    (net (code "179") (name "USB_CL_PRES") (class "Default")
      (node (ref "CN1") (pin "91") (pinfunction "USB_CL_PRES_91") (pintype "passive"))
    )
    (net (code "180") (name "WAKE#") (class "Default")
      (node (ref "CN1") (pin "17") (pinfunction "WAKE#_17") (pintype "passive"))
    )
    (net (code "181") (name "WDOUT") (class "Default")
      (node (ref "CN1") (pin "72") (pinfunction "WDOUT_72") (pintype "passive"))
    )
    (net (code "182") (name "WDTRIG#") (class "Default")
      (node (ref "CN1") (pin "70") (pinfunction "WDTRIG#_70") (pintype "passive"))
    )
    (net (code "183") (name "unconnected-(CN1-PadH1)") (class "Default")
      (node (ref "CN1") (pin "H1") (pinfunction "H1_H1") (pintype "passive"))
    )
    (net (code "184") (name "unconnected-(CN1-PadH2)") (class "Default")
      (node (ref "CN1") (pin "H2") (pinfunction "H2_H2") (pintype "passive"))
    )
    (net (code "185") (name "unconnected-(CN1-PadH3)") (class "Default")
      (node (ref "CN1") (pin "H3") (pinfunction "H3_H3") (pintype "passive"))
    )
    (net (code "186") (name "unconnected-(CN1-PadH4)") (class "Default")
      (node (ref "CN1") (pin "H4") (pinfunction "H4_H4") (pintype "passive"))
    )
    (net (code "187") (name "unconnected-(CN46-Pad2)") (class "Default")
      (node (ref "CN46") (pin "2") (pinfunction "2_2") (pintype "passive"))
    )
  )
)
